# Contactor_Switching.net
KiCad netlist of a schematic drawn in Altium Designer
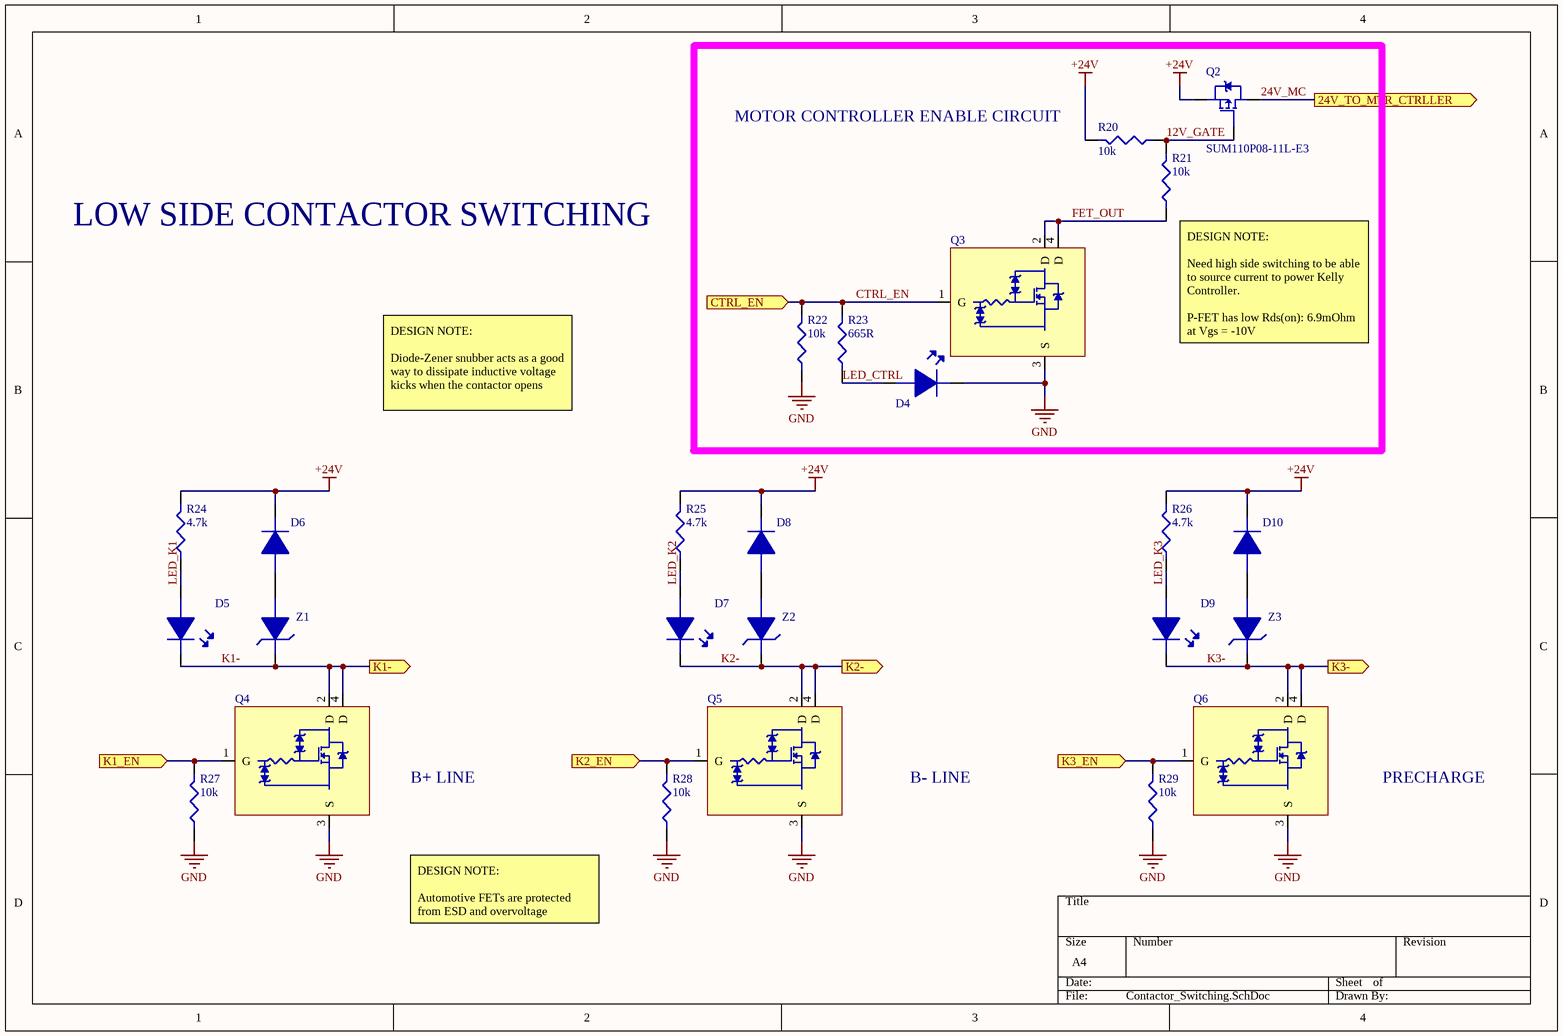
[diagram p0: Contactor_Switching.SchDoc]

(export (version "E")
  (design (tool "Eeschema 10.0.6"))
  (components
    (comp (ref "D4")
      (value "LTST-C191TBKT-5A")
      (footprint "LED_0603")
      (description "LED BLUE CLEAR 0603 SMD")
      (fields (field (name "MANUFACTURER") "Vishay Lite-On") (field (name "VOLTAGE") "29V"))
      (libsource (lib "PHANTOM_LIBRARY") (part "LTST-C191TBKT-5A"))
    )
    (comp (ref "D5")
      (value "LTST-C191TBKT-5A")
      (footprint "LED_0603")
      (description "LED BLUE CLEAR 0603 SMD")
      (fields (field (name "MANUFACTURER") "Vishay Lite-On") (field (name "VOLTAGE") "29V"))
      (libsource (lib "PHANTOM_LIBRARY") (part "LTST-C191TBKT-5A"))
    )
    (comp (ref "D6")
      (value "S3BB-TP")
      (footprint "DO-214AA_Diode")
      (description "DIODE GEN PURP 100V 3A DO214AA")
      (fields (field (name "MANUFACTURER") "MCC"))
      (libsource (lib "PHANTOM_LIBRARY") (part "S3BB-TP"))
    )
    (comp (ref "D7")
      (value "LTST-C191TBKT-5A")
      (footprint "LED_0603")
      (description "LED BLUE CLEAR 0603 SMD")
      (fields (field (name "MANUFACTURER") "Vishay Lite-On") (field (name "VOLTAGE") "29V"))
      (libsource (lib "PHANTOM_LIBRARY") (part "LTST-C191TBKT-5A"))
    )
    (comp (ref "D8")
      (value "S3BB-TP")
      (footprint "DO-214AA_Diode")
      (description "DIODE GEN PURP 100V 3A DO214AA")
      (fields (field (name "MANUFACTURER") "MCC"))
      (libsource (lib "PHANTOM_LIBRARY") (part "S3BB-TP"))
    )
    (comp (ref "D9")
      (value "LTST-C191TBKT-5A")
      (footprint "LED_0603")
      (description "LED BLUE CLEAR 0603 SMD")
      (fields (field (name "MANUFACTURER") "Vishay Lite-On") (field (name "VOLTAGE") "29V"))
      (libsource (lib "PHANTOM_LIBRARY") (part "LTST-C191TBKT-5A"))
    )
    (comp (ref "D10")
      (value "S3BB-TP")
      (footprint "DO-214AA_Diode")
      (description "DIODE GEN PURP 100V 3A DO214AA")
      (fields (field (name "MANUFACTURER") "MCC"))
      (libsource (lib "PHANTOM_LIBRARY") (part "S3BB-TP"))
    )
    (comp (ref "Q2")
      (value "SUM110P08-11L-E3")
      (footprint "D2PAK_FETs")
      (description "MOSFET P-CH 80V 23.5A 3-Pin(2+Tab) TO-263")
      (fields (field (name "MANUFACTURER") "Vishay"))
      (libsource (lib "PHANTOM_LIBRARY") (part "SUM110P08-11L-E3"))
    )
    (comp (ref "Q3")
      (value "NCV8406ASTT1G")
      (footprint "SOT-223_NFET")
      (description "MOSFET Self-Protected Low Side Driver Automotive 4-Pin(3+Tab) SOT-223 T/R")
      (fields (field (name "MANUFACTURER") "ON Semiconductor"))
      (libsource (lib "PHANTOM_LIBRARY") (part "NCV8406ASTT1G"))
    )
    (comp (ref "Q4")
      (value "NCV8406ASTT1G")
      (footprint "SOT-223_NFET")
      (description "MOSFET Self-Protected Low Side Driver Automotive 4-Pin(3+Tab) SOT-223 T/R")
      (fields (field (name "MANUFACTURER") "ON Semiconductor"))
      (libsource (lib "PHANTOM_LIBRARY") (part "NCV8406ASTT1G"))
    )
    (comp (ref "Q5")
      (value "NCV8406ASTT1G")
      (footprint "SOT-223_NFET")
      (description "MOSFET Self-Protected Low Side Driver Automotive 4-Pin(3+Tab) SOT-223 T/R")
      (fields (field (name "MANUFACTURER") "ON Semiconductor"))
      (libsource (lib "PHANTOM_LIBRARY") (part "NCV8406ASTT1G"))
    )
    (comp (ref "Q6")
      (value "NCV8406ASTT1G")
      (footprint "SOT-223_NFET")
      (description "MOSFET Self-Protected Low Side Driver Automotive 4-Pin(3+Tab) SOT-223 T/R")
      (fields (field (name "MANUFACTURER") "ON Semiconductor"))
      (libsource (lib "PHANTOM_LIBRARY") (part "NCV8406ASTT1G"))
    )
    (comp (ref "R20")
      (value "10k")
      (footprint "R0805")
      (description "RES SMD 10K OHM 1% 1/8W 0805")
      (fields
        (field (name "MANUFACTURER") "Yageo Phycomp")
        (field (name "MANUFACTURER PART NUMBER") "RC0805FR-071KL")
      )
      (libsource (lib "PHANTOM_LIBRARY") (part "RC0805FR-071KL"))
    )
    (comp (ref "R21")
      (value "10k")
      (footprint "R0805")
      (description "RES SMD 10K OHM 1% 1/8W 0805")
      (fields
        (field (name "MANUFACTURER") "Yageo Phycomp")
        (field (name "MANUFACTURER PART NUMBER") "RC0805FR-071KL")
      )
      (libsource (lib "PHANTOM_LIBRARY") (part "RC0805FR-071KL"))
    )
    (comp (ref "R22")
      (value "10k")
      (footprint "R0805")
      (description "RES SMD 10K OHM 1% 1/8W 0805")
      (fields
        (field (name "MANUFACTURER") "Yageo Phycomp")
        (field (name "MANUFACTURER PART NUMBER") "RC0805FR-071KL")
      )
      (libsource (lib "PHANTOM_LIBRARY") (part "RC0805FR-071KL"))
    )
    (comp (ref "R23")
      (value "665R")
      (footprint "R0805")
      (description "RES SMD 665 OHM 1% 1/8W 0805")
      (fields
        (field (name "MANUFACTURER") "Yageo")
        (field (name "MANUFACTURER PART NUMBER") "RC0805FR-07665RL")
      )
      (libsource (lib "PHANTOM_LIBRARY") (part "RC0805FR-07665RL"))
    )
    (comp (ref "R24")
      (value "4.7k")
      (footprint "R0805")
      (description "RES SMD 4.7K OHM 1% 1/8W 0805")
      (fields
        (field (name "MANUFACTURER") "Yageo")
        (field (name "MANUFACTURER PART NUMBER") "RC0805FR-074K7L")
      )
      (libsource (lib "PHANTOM_LIBRARY") (part "RC0805FR-074K7L"))
    )
    (comp (ref "R25")
      (value "4.7k")
      (footprint "R0805")
      (description "RES SMD 4.7K OHM 1% 1/8W 0805")
      (fields
        (field (name "MANUFACTURER") "Yageo")
        (field (name "MANUFACTURER PART NUMBER") "RC0805FR-074K7L")
      )
      (libsource (lib "PHANTOM_LIBRARY") (part "RC0805FR-074K7L"))
    )
    (comp (ref "R26")
      (value "4.7k")
      (footprint "R0805")
      (description "RES SMD 4.7K OHM 1% 1/8W 0805")
      (fields
        (field (name "MANUFACTURER") "Yageo")
        (field (name "MANUFACTURER PART NUMBER") "RC0805FR-074K7L")
      )
      (libsource (lib "PHANTOM_LIBRARY") (part "RC0805FR-074K7L"))
    )
    (comp (ref "R27")
      (value "10k")
      (footprint "R0805")
      (description "RES SMD 10K OHM 1% 1/8W 0805")
      (fields
        (field (name "MANUFACTURER") "Yageo Phycomp")
        (field (name "MANUFACTURER PART NUMBER") "RC0805FR-071KL")
      )
      (libsource (lib "PHANTOM_LIBRARY") (part "RC0805FR-071KL"))
    )
    (comp (ref "R28")
      (value "10k")
      (footprint "R0805")
      (description "RES SMD 10K OHM 1% 1/8W 0805")
      (fields
        (field (name "MANUFACTURER") "Yageo Phycomp")
        (field (name "MANUFACTURER PART NUMBER") "RC0805FR-071KL")
      )
      (libsource (lib "PHANTOM_LIBRARY") (part "RC0805FR-071KL"))
    )
    (comp (ref "R29")
      (value "10k")
      (footprint "R0805")
      (description "RES SMD 10K OHM 1% 1/8W 0805")
      (fields
        (field (name "MANUFACTURER") "Yageo Phycomp")
        (field (name "MANUFACTURER PART NUMBER") "RC0805FR-071KL")
      )
      (libsource (lib "PHANTOM_LIBRARY") (part "RC0805FR-071KL"))
    )
    (comp (ref "Z1")
      (value "12V")
      (footprint "DO-214AA_Diode")
      (description "DIODE ZENER 12V 5W DO214AA")
      (fields (field (name "MANUFACTURER") "MCC") (field (name "MANUFACTURER PART NUMBER") "SMBJ5349B-TP"))
      (libsource (lib "PHANTOM_LIBRARY") (part "SMBJ5349B-TP"))
    )
    (comp (ref "Z2")
      (value "12V")
      (footprint "DO-214AA_Diode")
      (description "DIODE ZENER 12V 5W DO214AA")
      (fields (field (name "MANUFACTURER") "MCC") (field (name "MANUFACTURER PART NUMBER") "SMBJ5349B-TP"))
      (libsource (lib "PHANTOM_LIBRARY") (part "SMBJ5349B-TP"))
    )
    (comp (ref "Z3")
      (value "12V")
      (footprint "DO-214AA_Diode")
      (description "DIODE ZENER 12V 5W DO214AA")
      (fields (field (name "MANUFACTURER") "MCC") (field (name "MANUFACTURER PART NUMBER") "SMBJ5349B-TP"))
      (libsource (lib "PHANTOM_LIBRARY") (part "SMBJ5349B-TP"))
    )
  )
  (nets
    (net (code "1") (name "+24V") (class "Default")
      (node (ref "D10") (pin "2") (pinfunction "2_2") (pintype "passive"))
      (node (ref "D6") (pin "2") (pinfunction "2_2") (pintype "passive"))
      (node (ref "D8") (pin "2") (pinfunction "2_2") (pintype "passive"))
      (node (ref "Q2") (pin "4") (pinfunction "4_4") (pintype "passive"))
      (node (ref "R20") (pin "2") (pinfunction "2_2") (pintype "passive"))
      (node (ref "R24") (pin "2") (pinfunction "2_2") (pintype "passive"))
      (node (ref "R25") (pin "2") (pinfunction "2_2") (pintype "passive"))
      (node (ref "R26") (pin "2") (pinfunction "2_2") (pintype "passive"))
    )
    (net (code "2") (name "/12V_GATE") (class "Default")
      (node (ref "Q2") (pin "1") (pinfunction "1_1") (pintype "passive"))
      (node (ref "R20") (pin "1") (pinfunction "1_1") (pintype "passive"))
      (node (ref "R21") (pin "2") (pinfunction "2_2") (pintype "passive"))
    )
    (net (code "3") (name "/24V_MC") (class "Default")
      (node (ref "Q2") (pin "3") (pinfunction "3_3") (pintype "passive"))
    )
    (net (code "4") (name "/CTRL_EN") (class "Default")
      (node (ref "Q3") (pin "1") (pinfunction "G_1") (pintype "passive"))
      (node (ref "R22") (pin "2") (pinfunction "2_2") (pintype "passive"))
      (node (ref "R23") (pin "2") (pinfunction "2_2") (pintype "passive"))
    )
    (net (code "5") (name "/FET_OUT") (class "Default")
      (node (ref "Q3") (pin "2") (pinfunction "D_2") (pintype "passive"))
      (node (ref "Q3") (pin "4") (pinfunction "D_4") (pintype "passive"))
      (node (ref "R21") (pin "1") (pinfunction "1_1") (pintype "passive"))
    )
    (net (code "6") (name "/K1-") (class "Default")
      (node (ref "D5") (pin "2") (pinfunction "2_2") (pintype "passive"))
      (node (ref "Q4") (pin "2") (pinfunction "D_2") (pintype "passive"))
      (node (ref "Q4") (pin "4") (pinfunction "D_4") (pintype "passive"))
      (node (ref "Z1") (pin "2") (pinfunction "2_2") (pintype "passive"))
    )
    (net (code "7") (name "/K1_EN") (class "Default")
      (node (ref "Q4") (pin "1") (pinfunction "G_1") (pintype "passive"))
      (node (ref "R27") (pin "2") (pinfunction "2_2") (pintype "passive"))
    )
    (net (code "8") (name "/K2-") (class "Default")
      (node (ref "D7") (pin "2") (pinfunction "2_2") (pintype "passive"))
      (node (ref "Q5") (pin "2") (pinfunction "D_2") (pintype "passive"))
      (node (ref "Q5") (pin "4") (pinfunction "D_4") (pintype "passive"))
      (node (ref "Z2") (pin "2") (pinfunction "2_2") (pintype "passive"))
    )
    (net (code "9") (name "/K2_EN") (class "Default")
      (node (ref "Q5") (pin "1") (pinfunction "G_1") (pintype "passive"))
      (node (ref "R28") (pin "2") (pinfunction "2_2") (pintype "passive"))
    )
    (net (code "10") (name "/K3-") (class "Default")
      (node (ref "D9") (pin "2") (pinfunction "2_2") (pintype "passive"))
      (node (ref "Q6") (pin "2") (pinfunction "D_2") (pintype "passive"))
      (node (ref "Q6") (pin "4") (pinfunction "D_4") (pintype "passive"))
      (node (ref "Z3") (pin "2") (pinfunction "2_2") (pintype "passive"))
    )
    (net (code "11") (name "/K3_EN") (class "Default")
      (node (ref "Q6") (pin "1") (pinfunction "G_1") (pintype "passive"))
      (node (ref "R29") (pin "2") (pinfunction "2_2") (pintype "passive"))
    )
    (net (code "12") (name "/LED_CTRL") (class "Default")
      (node (ref "D4") (pin "1") (pinfunction "1_1") (pintype "passive"))
      (node (ref "R23") (pin "1") (pinfunction "1_1") (pintype "passive"))
    )
    (net (code "13") (name "/LED_K1") (class "Default")
      (node (ref "D5") (pin "1") (pinfunction "1_1") (pintype "passive"))
      (node (ref "R24") (pin "1") (pinfunction "1_1") (pintype "passive"))
    )
    (net (code "14") (name "/LED_K2") (class "Default")
      (node (ref "D7") (pin "1") (pinfunction "1_1") (pintype "passive"))
      (node (ref "R25") (pin "1") (pinfunction "1_1") (pintype "passive"))
    )
    (net (code "15") (name "/LED_K3") (class "Default")
      (node (ref "D9") (pin "1") (pinfunction "1_1") (pintype "passive"))
      (node (ref "R26") (pin "1") (pinfunction "1_1") (pintype "passive"))
    )
    (net (code "16") (name "GND") (class "Default")
      (node (ref "D4") (pin "2") (pinfunction "2_2") (pintype "passive"))
      (node (ref "Q3") (pin "3") (pinfunction "S_3") (pintype "passive"))
      (node (ref "Q4") (pin "3") (pinfunction "S_3") (pintype "passive"))
      (node (ref "Q5") (pin "3") (pinfunction "S_3") (pintype "passive"))
      (node (ref "Q6") (pin "3") (pinfunction "S_3") (pintype "passive"))
      (node (ref "R22") (pin "1") (pinfunction "1_1") (pintype "passive"))
      (node (ref "R27") (pin "1") (pinfunction "1_1") (pintype "passive"))
      (node (ref "R28") (pin "1") (pinfunction "1_1") (pintype "passive"))
      (node (ref "R29") (pin "1") (pinfunction "1_1") (pintype "passive"))
    )
    (net (code "17") (name "Net-(D6-Pad1)") (class "Default")
      (node (ref "D6") (pin "1") (pinfunction "1_1") (pintype "passive"))
      (node (ref "Z1") (pin "1") (pinfunction "1_1") (pintype "passive"))
    )
    (net (code "18") (name "Net-(D8-Pad1)") (class "Default")
      (node (ref "D8") (pin "1") (pinfunction "1_1") (pintype "passive"))
      (node (ref "Z2") (pin "1") (pinfunction "1_1") (pintype "passive"))
    )
    (net (code "19") (name "Net-(D10-Pad1)") (class "Default")
      (node (ref "D10") (pin "1") (pinfunction "1_1") (pintype "passive"))
      (node (ref "Z3") (pin "1") (pinfunction "1_1") (pintype "passive"))
    )
  )
)
